# iridia-tam-right-board.net
KiCad netlist of a schematic drawn in EAGLE
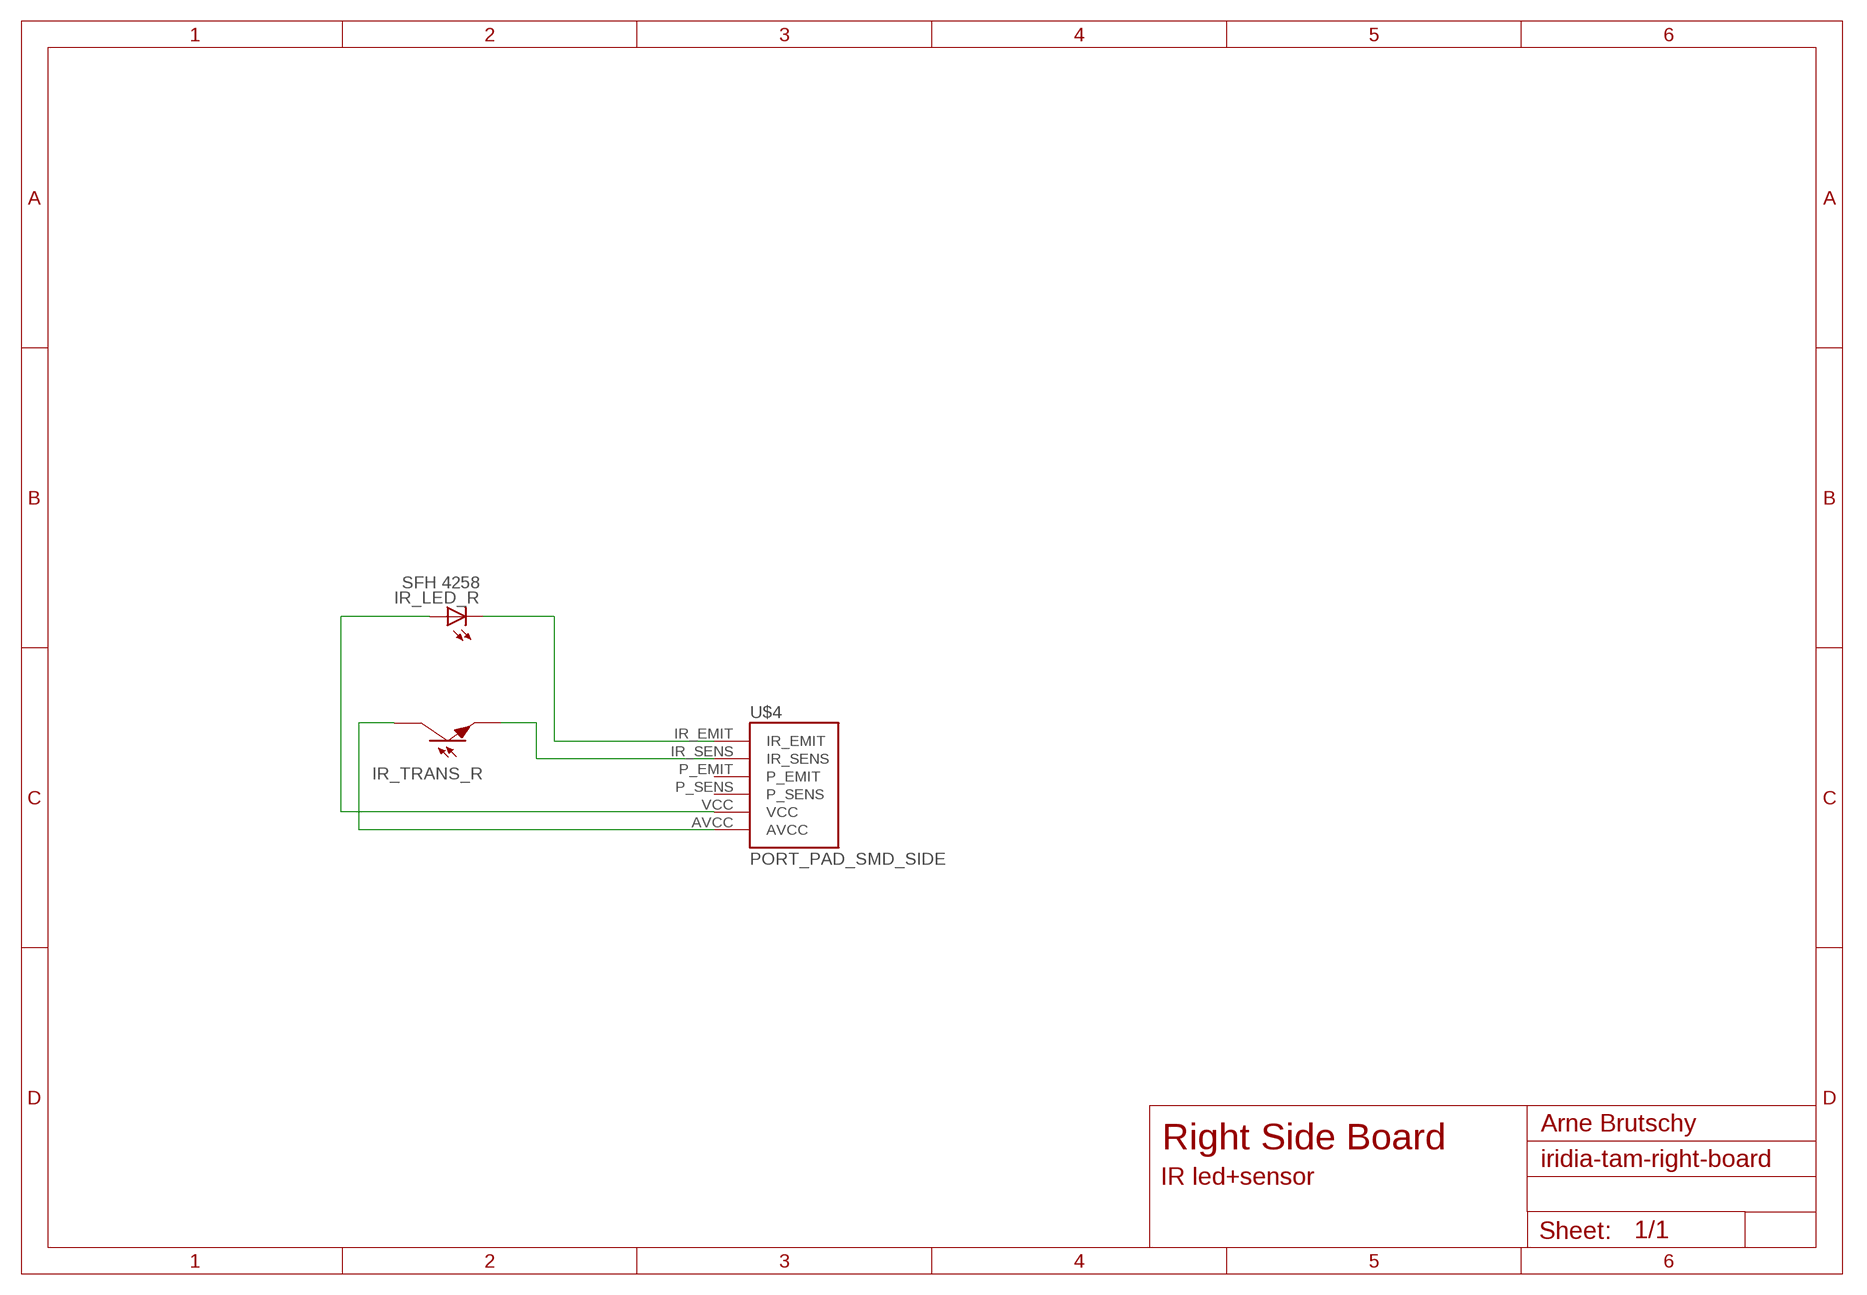
[diagram p0: schematic, sheet 1]

(export (version "E")
  (design (tool "Eeschema 10.0.6"))
  (components
    (comp (ref "IR_LED_R")
      (value "SFH 4258")
      (footprint "eagle-import:P-LCC-4-1C-3A")
      (libsource (lib "eagle-import") (part "LEDP-LCC-4"))
    )
    (comp (ref "IR_TRANS_R")
      (value "SFH 320 FA")
      (footprint "eagle-import:P-LCC-2-TRANS")
      (libsource (lib "eagle-import") (part "IR_TRANSP-LCC-2"))
    )
    (comp (ref "U$4")
      (value "PORT_PAD_SMD_SIDE")
      (footprint "eagle-import:PORT_PAD_SMD_SIDE")
      (libsource (lib "eagle-import") (part "PORT_PAD_SMD_SIDE"))
    )
  )
  (nets
    (net (code "1") (name "Net-(IR_LED_R-A-PadA@2)") (class "Default")
      (node (ref "IR_LED_R") (pin "A@2") (pinfunction "A_A@2") (pintype "passive"))
      (node (ref "IR_LED_R") (pin "A@3") (pinfunction "A_A@3") (pintype "passive"))
      (node (ref "IR_LED_R") (pin "A@4") (pinfunction "A_A@4") (pintype "passive"))
      (node (ref "U$4") (pin "VCC") (pinfunction "VCC_VCC") (pintype "bidirectional"))
    )
    (net (code "2") (name "Net-(IR_LED_R-C)") (class "Default")
      (node (ref "IR_LED_R") (pin "C@1") (pinfunction "C_C@1") (pintype "passive"))
      (node (ref "U$4") (pin "IR_EMIT") (pinfunction "IR_EMIT_IR_EMIT") (pintype "bidirectional"))
    )
    (net (code "3") (name "Net-(IR_TRANS_R-PadCOL)") (class "Default")
      (node (ref "IR_TRANS_R") (pin "COL") (pinfunction "COL_COL") (pintype "passive"))
      (node (ref "U$4") (pin "AVCC") (pinfunction "AVCC_AVCC") (pintype "bidirectional"))
    )
    (net (code "4") (name "Net-(IR_TRANS_R-PadE)") (class "Default")
      (node (ref "IR_TRANS_R") (pin "E") (pinfunction "E_E") (pintype "passive"))
      (node (ref "U$4") (pin "IR_SENS") (pinfunction "IR_SENS_IR_SENS") (pintype "bidirectional"))
    )
    (net (code "5") (name "unconnected-(U$4-PadP_EMIT)") (class "Default")
      (node (ref "U$4") (pin "P_EMIT") (pinfunction "P_EMIT_P_EMIT") (pintype "bidirectional"))
    )
    (net (code "6") (name "unconnected-(U$4-PadP_SENS)") (class "Default")
      (node (ref "U$4") (pin "P_SENS") (pinfunction "P_SENS_P_SENS") (pintype "bidirectional"))
    )
  )
)
